# board.net
KiCad netlist of a schematic drawn in EAGLE
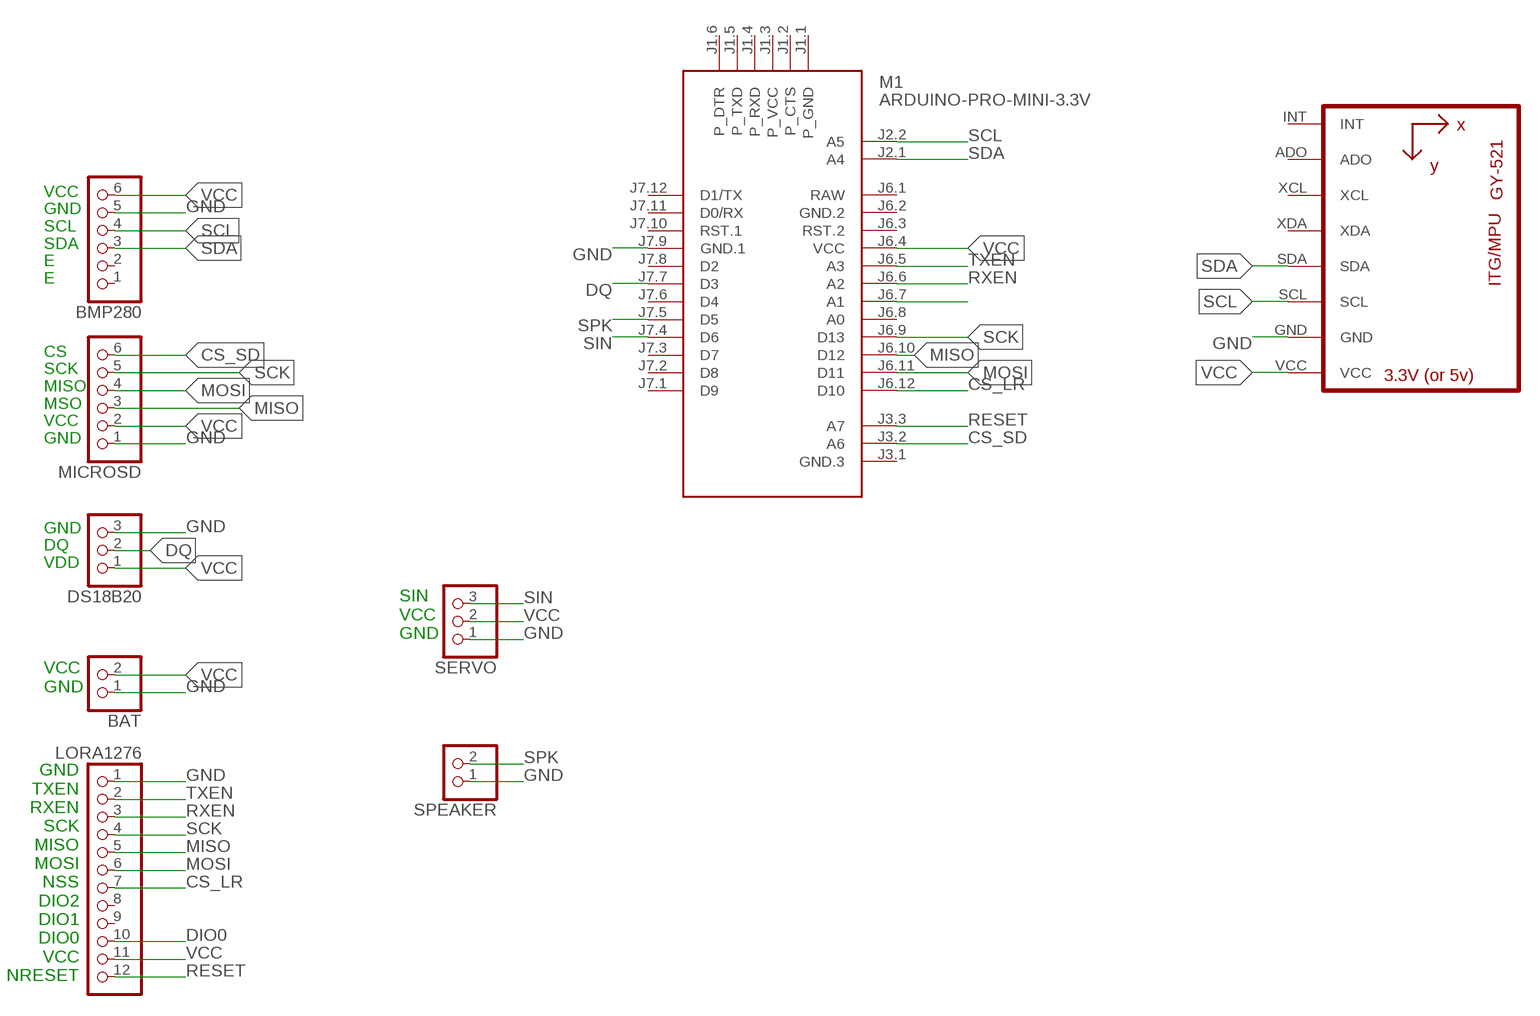
[diagram p0: schematic, sheet 1]

(export (version "E")
  (design (tool "Eeschema 10.0.6"))
  (components
    (comp (ref "BAT")
      (value "PINHD-1X2")
      (footprint "eagle-import:1X02")
      (libsource (lib "eagle-import") (part "PINHD-1X2"))
    )
    (comp (ref "BMP280")
      (value "PINHD-1X6")
      (footprint "eagle-import:1X06")
      (libsource (lib "eagle-import") (part "PINHD-1X6"))
    )
    (comp (ref "DS18B20")
      (value "PINHD-1X3")
      (footprint "eagle-import:1X03")
      (libsource (lib "eagle-import") (part "PINHD-1X3"))
    )
    (comp (ref "LORA1276")
      (value "PINHD-1X12")
      (footprint "eagle-import:1X12")
      (libsource (lib "eagle-import") (part "PINHD-1X12"))
    )
    (comp (ref "M1")
      (value "ARDUINO-PRO-MINI-3.3V")
      (footprint "eagle-import:ARDUINO-PRO-MINI")
      (libsource (lib "eagle-import") (part "ARDUINO-PRO-MINI-3.3V"))
    )
    (comp (ref "MICROSD")
      (value "PINHD-1X6")
      (footprint "eagle-import:1X06")
      (libsource (lib "eagle-import") (part "PINHD-1X6"))
    )
    (comp (ref "SERVO")
      (value "PINHD-1X3")
      (footprint "eagle-import:1X03")
      (libsource (lib "eagle-import") (part "PINHD-1X3"))
    )
    (comp (ref "SPEAKER")
      (value "PINHD-1X2")
      (footprint "eagle-import:1X02")
      (libsource (lib "eagle-import") (part "PINHD-1X2"))
    )
    (comp (ref "U1")
      (value "GY-521MPU6050")
      (footprint "eagle-import:GY-521")
      (libsource (lib "eagle-import") (part "GY-521MPU6050"))
    )
  )
  (nets
    (net (code "1") (name "/CS_LR") (class "Default")
      (node (ref "LORA1276") (pin "7") (pinfunction "7_7") (pintype "passive"))
      (node (ref "M1") (pin "J6.12") (pinfunction "D10_J6.12") (pintype "bidirectional"))
    )
    (net (code "2") (name "/DIO0") (class "Default")
      (node (ref "LORA1276") (pin "10") (pinfunction "10_10") (pintype "passive"))
      (node (ref "M1") (pin "J6.7") (pinfunction "A1_J6.7") (pintype "bidirectional"))
    )
    (net (code "3") (name "/GND") (class "Default")
      (node (ref "BAT") (pin "1") (pinfunction "1_1") (pintype "passive"))
      (node (ref "BMP280") (pin "5") (pinfunction "5_5") (pintype "passive"))
      (node (ref "DS18B20") (pin "3") (pinfunction "3_3") (pintype "passive"))
      (node (ref "LORA1276") (pin "1") (pinfunction "1_1") (pintype "passive"))
      (node (ref "M1") (pin "J7.9") (pinfunction "GND.1_J7.9") (pintype "power_in"))
      (node (ref "MICROSD") (pin "1") (pinfunction "1_1") (pintype "passive"))
      (node (ref "SERVO") (pin "1") (pinfunction "1_1") (pintype "passive"))
      (node (ref "SPEAKER") (pin "1") (pinfunction "1_1") (pintype "passive"))
      (node (ref "U1") (pin "GND") (pinfunction "GND_GND") (pintype "bidirectional"))
    )
    (net (code "4") (name "/GND.2") (class "Default")
      (node (ref "M1") (pin "J6.2") (pinfunction "GND.2_J6.2") (pintype "power_in"))
    )
    (net (code "5") (name "/RAW") (class "Default")
      (node (ref "M1") (pin "J6.1") (pinfunction "RAW_J6.1") (pintype "power_in"))
    )
    (net (code "6") (name "/RESET") (class "Default")
      (node (ref "LORA1276") (pin "12") (pinfunction "12_12") (pintype "passive"))
      (node (ref "M1") (pin "J3.3") (pinfunction "A7_J3.3") (pintype "bidirectional"))
    )
    (net (code "7") (name "/RXEN") (class "Default")
      (node (ref "LORA1276") (pin "3") (pinfunction "3_3") (pintype "passive"))
      (node (ref "M1") (pin "J6.6") (pinfunction "A2_J6.6") (pintype "bidirectional"))
    )
    (net (code "8") (name "/SIN") (class "Default")
      (node (ref "M1") (pin "J7.4") (pinfunction "D6_J7.4") (pintype "bidirectional"))
      (node (ref "SERVO") (pin "3") (pinfunction "3_3") (pintype "passive"))
    )
    (net (code "9") (name "/SPK") (class "Default")
      (node (ref "M1") (pin "J7.5") (pinfunction "D5_J7.5") (pintype "bidirectional"))
      (node (ref "SPEAKER") (pin "2") (pinfunction "2_2") (pintype "passive"))
    )
    (net (code "10") (name "/TXEN") (class "Default")
      (node (ref "LORA1276") (pin "2") (pinfunction "2_2") (pintype "passive"))
      (node (ref "M1") (pin "J6.5") (pinfunction "A3_J6.5") (pintype "bidirectional"))
    )
    (net (code "11") (name "CS_SD") (class "Default")
      (node (ref "M1") (pin "J3.2") (pinfunction "A6_J3.2") (pintype "bidirectional"))
      (node (ref "MICROSD") (pin "6") (pinfunction "6_6") (pintype "passive"))
    )
    (net (code "12") (name "DQ") (class "Default")
      (node (ref "DS18B20") (pin "2") (pinfunction "2_2") (pintype "passive"))
      (node (ref "M1") (pin "J7.7") (pinfunction "D3_J7.7") (pintype "bidirectional"))
    )
    (net (code "13") (name "MISO") (class "Default")
      (node (ref "LORA1276") (pin "5") (pinfunction "5_5") (pintype "passive"))
      (node (ref "M1") (pin "J6.10") (pinfunction "D12_J6.10") (pintype "bidirectional"))
      (node (ref "MICROSD") (pin "3") (pinfunction "3_3") (pintype "passive"))
    )
    (net (code "14") (name "MOSI") (class "Default")
      (node (ref "LORA1276") (pin "6") (pinfunction "6_6") (pintype "passive"))
      (node (ref "M1") (pin "J6.11") (pinfunction "D11_J6.11") (pintype "bidirectional"))
      (node (ref "MICROSD") (pin "4") (pinfunction "4_4") (pintype "passive"))
    )
    (net (code "15") (name "SCK") (class "Default")
      (node (ref "LORA1276") (pin "4") (pinfunction "4_4") (pintype "passive"))
      (node (ref "M1") (pin "J6.9") (pinfunction "D13_J6.9") (pintype "bidirectional"))
      (node (ref "MICROSD") (pin "5") (pinfunction "5_5") (pintype "passive"))
    )
    (net (code "16") (name "SCL") (class "Default")
      (node (ref "BMP280") (pin "4") (pinfunction "4_4") (pintype "passive"))
      (node (ref "M1") (pin "J2.2") (pinfunction "A5_J2.2") (pintype "bidirectional"))
      (node (ref "U1") (pin "SCL") (pinfunction "SCL_SCL") (pintype "bidirectional"))
    )
    (net (code "17") (name "SDA") (class "Default")
      (node (ref "BMP280") (pin "3") (pinfunction "3_3") (pintype "passive"))
      (node (ref "M1") (pin "J2.1") (pinfunction "A4_J2.1") (pintype "bidirectional"))
      (node (ref "U1") (pin "SDA") (pinfunction "SDA_SDA") (pintype "bidirectional"))
    )
    (net (code "18") (name "VCC") (class "Default")
      (node (ref "BAT") (pin "2") (pinfunction "2_2") (pintype "passive"))
      (node (ref "BMP280") (pin "6") (pinfunction "6_6") (pintype "passive"))
      (node (ref "DS18B20") (pin "1") (pinfunction "1_1") (pintype "passive"))
      (node (ref "LORA1276") (pin "11") (pinfunction "11_11") (pintype "passive"))
      (node (ref "M1") (pin "J6.4") (pinfunction "VCC_J6.4") (pintype "power_in"))
      (node (ref "MICROSD") (pin "2") (pinfunction "2_2") (pintype "passive"))
      (node (ref "SERVO") (pin "2") (pinfunction "2_2") (pintype "passive"))
      (node (ref "U1") (pin "VCC") (pinfunction "VCC_VCC") (pintype "bidirectional"))
    )
    (net (code "19") (name "unconnected-(BMP280-Pad1)") (class "Default")
      (node (ref "BMP280") (pin "1") (pinfunction "1_1") (pintype "passive"))
    )
    (net (code "20") (name "unconnected-(BMP280-Pad2)") (class "Default")
      (node (ref "BMP280") (pin "2") (pinfunction "2_2") (pintype "passive"))
    )
    (net (code "21") (name "unconnected-(LORA1276-Pad8)") (class "Default")
      (node (ref "LORA1276") (pin "8") (pinfunction "8_8") (pintype "passive"))
    )
    (net (code "22") (name "unconnected-(LORA1276-Pad9)") (class "Default")
      (node (ref "LORA1276") (pin "9") (pinfunction "9_9") (pintype "passive"))
    )
    (net (code "23") (name "unconnected-(M1-A0-PadJ6.8)") (class "Default")
      (node (ref "M1") (pin "J6.8") (pinfunction "A0_J6.8") (pintype "bidirectional"))
    )
    (net (code "24") (name "unconnected-(M1-D0{slash}RX-PadJ7.11)") (class "Default")
      (node (ref "M1") (pin "J7.11") (pinfunction "D0/RX_J7.11") (pintype "bidirectional"))
    )
    (net (code "25") (name "unconnected-(M1-D1{slash}TX-PadJ7.12)") (class "Default")
      (node (ref "M1") (pin "J7.12") (pinfunction "D1/TX_J7.12") (pintype "bidirectional"))
    )
    (net (code "26") (name "unconnected-(M1-D2-PadJ7.8)") (class "Default")
      (node (ref "M1") (pin "J7.8") (pinfunction "D2_J7.8") (pintype "bidirectional"))
    )
    (net (code "27") (name "unconnected-(M1-D4-PadJ7.6)") (class "Default")
      (node (ref "M1") (pin "J7.6") (pinfunction "D4_J7.6") (pintype "bidirectional"))
    )
    (net (code "28") (name "unconnected-(M1-D7-PadJ7.3)") (class "Default")
      (node (ref "M1") (pin "J7.3") (pinfunction "D7_J7.3") (pintype "bidirectional"))
    )
    (net (code "29") (name "unconnected-(M1-D8-PadJ7.2)") (class "Default")
      (node (ref "M1") (pin "J7.2") (pinfunction "D8_J7.2") (pintype "bidirectional"))
    )
    (net (code "30") (name "unconnected-(M1-D9-PadJ7.1)") (class "Default")
      (node (ref "M1") (pin "J7.1") (pinfunction "D9_J7.1") (pintype "bidirectional"))
    )
    (net (code "31") (name "unconnected-(M1-GND.3-PadJ3.1)") (class "Default")
      (node (ref "M1") (pin "J3.1") (pinfunction "GND.3_J3.1") (pintype "bidirectional"))
    )
    (net (code "32") (name "unconnected-(M1-P_CTS-PadJ1.2)") (class "Default")
      (node (ref "M1") (pin "J1.2") (pinfunction "P_CTS_J1.2") (pintype "bidirectional"))
    )
    (net (code "33") (name "unconnected-(M1-P_DTR-PadJ1.6)") (class "Default")
      (node (ref "M1") (pin "J1.6") (pinfunction "P_DTR_J1.6") (pintype "bidirectional"))
    )
    (net (code "34") (name "unconnected-(M1-P_GND-PadJ1.1)") (class "Default")
      (node (ref "M1") (pin "J1.1") (pinfunction "P_GND_J1.1") (pintype "bidirectional"))
    )
    (net (code "35") (name "unconnected-(M1-P_RXD-PadJ1.4)") (class "Default")
      (node (ref "M1") (pin "J1.4") (pinfunction "P_RXD_J1.4") (pintype "bidirectional"))
    )
    (net (code "36") (name "unconnected-(M1-P_TXD-PadJ1.5)") (class "Default")
      (node (ref "M1") (pin "J1.5") (pinfunction "P_TXD_J1.5") (pintype "bidirectional"))
    )
    (net (code "37") (name "unconnected-(M1-P_VCC-PadJ1.3)") (class "Default")
      (node (ref "M1") (pin "J1.3") (pinfunction "P_VCC_J1.3") (pintype "bidirectional"))
    )
    (net (code "38") (name "unconnected-(M1-RST.1-PadJ7.10)") (class "Default")
      (node (ref "M1") (pin "J7.10") (pinfunction "RST.1_J7.10") (pintype "bidirectional"))
    )
    (net (code "39") (name "unconnected-(M1-RST.2-PadJ6.3)") (class "Default")
      (node (ref "M1") (pin "J6.3") (pinfunction "RST.2_J6.3") (pintype "bidirectional"))
    )
    (net (code "40") (name "unconnected-(U1-PadADO)") (class "Default")
      (node (ref "U1") (pin "ADO") (pinfunction "ADO_ADO") (pintype "bidirectional"))
    )
    (net (code "41") (name "unconnected-(U1-PadINT)") (class "Default")
      (node (ref "U1") (pin "INT") (pinfunction "INT_INT") (pintype "bidirectional"))
    )
    (net (code "42") (name "unconnected-(U1-PadXCL)") (class "Default")
      (node (ref "U1") (pin "XCL") (pinfunction "XCL_XCL") (pintype "bidirectional"))
    )
    (net (code "43") (name "unconnected-(U1-PadXDA)") (class "Default")
      (node (ref "U1") (pin "XDA") (pinfunction "XDA_XDA") (pintype "bidirectional"))
    )
  )
)
